# Voltage_converter_5V.net
KiCad netlist of a schematic drawn in EAGLE
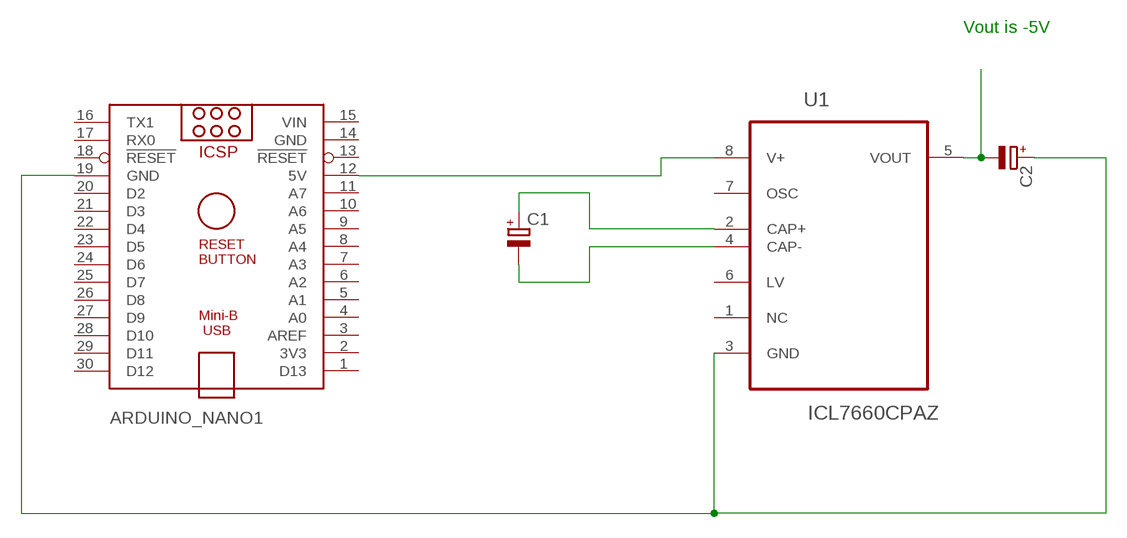
[diagram p0: schematic, sheet 1]

(export (version "E")
  (design (tool "Eeschema 10.0.6"))
  (components
    (comp (ref "ARDUINO_NANO1")
      (value "ARDUINO_NANO")
      (footprint "eagle-import:ARDUINO_NANO")
      (libsource (lib "eagle-import") (part "ARDUINO_NANO"))
    )
    (comp (ref "C1")
      (value "CPOL-EUE1.8-4")
      (footprint "eagle-import:E1,8-4")
      (libsource (lib "eagle-import") (part "CPOL-EUE1.8-4"))
    )
    (comp (ref "C2")
      (value "CPOL-EUE1.8-4")
      (footprint "eagle-import:E1,8-4")
      (libsource (lib "eagle-import") (part "CPOL-EUE1.8-4"))
    )
    (comp (ref "U1")
      (value "ICL7660CPAZ")
      (footprint "eagle-import:DIP254P762X533-8")
      (fields (field (name "MF") "Renesas Electronics"))
      (libsource (lib "eagle-import") (part "ICL7660CPAZ"))
    )
  )
  (nets
    (net (code "1") (name "/GND") (class "Default")
      (node (ref "ARDUINO_NANO1") (pin "14") (pinfunction "GND_14") (pintype "power_in"))
    )
    (net (code "2") (name "/VIN") (class "Default")
      (node (ref "ARDUINO_NANO1") (pin "15") (pinfunction "VIN_15") (pintype "power_in"))
    )
    (net (code "3") (name "Net-(ARDUINO_NANO1-5V)") (class "Default")
      (node (ref "ARDUINO_NANO1") (pin "12") (pinfunction "5V_12") (pintype "power_in"))
      (node (ref "U1") (pin "8") (pinfunction "V+_8") (pintype "power_in"))
    )
    (net (code "4") (name "Net-(U1-CAP+)") (class "Default")
      (node (ref "C1") (pin "+") (pinfunction "+_+") (pintype "passive"))
      (node (ref "U1") (pin "2") (pinfunction "CAP+_2") (pintype "input"))
    )
    (net (code "5") (name "Net-(U1-CAP-)") (class "Default")
      (node (ref "C1") (pin "-") (pinfunction "-_-") (pintype "passive"))
      (node (ref "U1") (pin "4") (pinfunction "CAP-_4") (pintype "input"))
    )
    (net (code "6") (name "Net-(U1-GND)") (class "Default")
      (node (ref "ARDUINO_NANO1") (pin "19") (pinfunction "GND_19") (pintype "power_in"))
      (node (ref "C2") (pin "+") (pinfunction "+_+") (pintype "passive"))
      (node (ref "U1") (pin "3") (pinfunction "GND_3") (pintype "passive"))
    )
    (net (code "7") (name "Net-(U1-VOUT)") (class "Default")
      (node (ref "C2") (pin "-") (pinfunction "-_-") (pintype "passive"))
      (node (ref "U1") (pin "5") (pinfunction "VOUT_5") (pintype "output"))
    )
    (net (code "8") (name "unconnected-(ARDUINO_NANO1-3V3-Pad2)") (class "Default")
      (node (ref "ARDUINO_NANO1") (pin "2") (pinfunction "3V3_2") (pintype "output"))
    )
    (net (code "9") (name "unconnected-(ARDUINO_NANO1-A0-Pad4)") (class "Default")
      (node (ref "ARDUINO_NANO1") (pin "4") (pinfunction "A0_4") (pintype "bidirectional"))
    )
    (net (code "10") (name "unconnected-(ARDUINO_NANO1-A1-Pad5)") (class "Default")
      (node (ref "ARDUINO_NANO1") (pin "5") (pinfunction "A1_5") (pintype "bidirectional"))
    )
    (net (code "11") (name "unconnected-(ARDUINO_NANO1-A2-Pad6)") (class "Default")
      (node (ref "ARDUINO_NANO1") (pin "6") (pinfunction "A2_6") (pintype "bidirectional"))
    )
    (net (code "12") (name "unconnected-(ARDUINO_NANO1-A3-Pad7)") (class "Default")
      (node (ref "ARDUINO_NANO1") (pin "7") (pinfunction "A3_7") (pintype "bidirectional"))
    )
    (net (code "13") (name "unconnected-(ARDUINO_NANO1-A4-Pad8)") (class "Default")
      (node (ref "ARDUINO_NANO1") (pin "8") (pinfunction "A4_8") (pintype "bidirectional"))
    )
    (net (code "14") (name "unconnected-(ARDUINO_NANO1-A5-Pad9)") (class "Default")
      (node (ref "ARDUINO_NANO1") (pin "9") (pinfunction "A5_9") (pintype "bidirectional"))
    )
    (net (code "15") (name "unconnected-(ARDUINO_NANO1-A6-Pad10)") (class "Default")
      (node (ref "ARDUINO_NANO1") (pin "10") (pinfunction "A6_10") (pintype "bidirectional"))
    )
    (net (code "16") (name "unconnected-(ARDUINO_NANO1-A7-Pad11)") (class "Default")
      (node (ref "ARDUINO_NANO1") (pin "11") (pinfunction "A7_11") (pintype "bidirectional"))
    )
    (net (code "17") (name "unconnected-(ARDUINO_NANO1-AREF-Pad3)") (class "Default")
      (node (ref "ARDUINO_NANO1") (pin "3") (pinfunction "AREF_3") (pintype "input"))
    )
    (net (code "18") (name "unconnected-(ARDUINO_NANO1-D2-Pad20)") (class "Default")
      (node (ref "ARDUINO_NANO1") (pin "20") (pinfunction "D2_20") (pintype "bidirectional"))
    )
    (net (code "19") (name "unconnected-(ARDUINO_NANO1-D3-Pad21)") (class "Default")
      (node (ref "ARDUINO_NANO1") (pin "21") (pinfunction "D3_21") (pintype "bidirectional"))
    )
    (net (code "20") (name "unconnected-(ARDUINO_NANO1-D4-Pad22)") (class "Default")
      (node (ref "ARDUINO_NANO1") (pin "22") (pinfunction "D4_22") (pintype "bidirectional"))
    )
    (net (code "21") (name "unconnected-(ARDUINO_NANO1-D5-Pad23)") (class "Default")
      (node (ref "ARDUINO_NANO1") (pin "23") (pinfunction "D5_23") (pintype "bidirectional"))
    )
    (net (code "22") (name "unconnected-(ARDUINO_NANO1-D6-Pad24)") (class "Default")
      (node (ref "ARDUINO_NANO1") (pin "24") (pinfunction "D6_24") (pintype "bidirectional"))
    )
    (net (code "23") (name "unconnected-(ARDUINO_NANO1-D7-Pad25)") (class "Default")
      (node (ref "ARDUINO_NANO1") (pin "25") (pinfunction "D7_25") (pintype "bidirectional"))
    )
    (net (code "24") (name "unconnected-(ARDUINO_NANO1-D8-Pad26)") (class "Default")
      (node (ref "ARDUINO_NANO1") (pin "26") (pinfunction "D8_26") (pintype "bidirectional"))
    )
    (net (code "25") (name "unconnected-(ARDUINO_NANO1-D9-Pad27)") (class "Default")
      (node (ref "ARDUINO_NANO1") (pin "27") (pinfunction "D9_27") (pintype "bidirectional"))
    )
    (net (code "26") (name "unconnected-(ARDUINO_NANO1-D10-Pad28)") (class "Default")
      (node (ref "ARDUINO_NANO1") (pin "28") (pinfunction "D10_28") (pintype "bidirectional"))
    )
    (net (code "27") (name "unconnected-(ARDUINO_NANO1-D11-Pad29)") (class "Default")
      (node (ref "ARDUINO_NANO1") (pin "29") (pinfunction "D11_29") (pintype "bidirectional"))
    )
    (net (code "28") (name "unconnected-(ARDUINO_NANO1-D12-Pad30)") (class "Default")
      (node (ref "ARDUINO_NANO1") (pin "30") (pinfunction "D12_30") (pintype "bidirectional"))
    )
    (net (code "29") (name "unconnected-(ARDUINO_NANO1-D13-Pad1)") (class "Default")
      (node (ref "ARDUINO_NANO1") (pin "1") (pinfunction "D13_1") (pintype "bidirectional"))
    )
    (net (code "30") (name "unconnected-(ARDUINO_NANO1-RX0-Pad17)") (class "Default")
      (node (ref "ARDUINO_NANO1") (pin "17") (pinfunction "RX0_17") (pintype "bidirectional"))
    )
    (net (code "31") (name "unconnected-(ARDUINO_NANO1-TX1-Pad16)") (class "Default")
      (node (ref "ARDUINO_NANO1") (pin "16") (pinfunction "TX1_16") (pintype "bidirectional"))
    )
    (net (code "32") (name "unconnected-(ARDUINO_NANO1-~{RESET}-Pad13)") (class "Default")
      (node (ref "ARDUINO_NANO1") (pin "13") (pinfunction "~{RESET}_13") (pintype "input"))
    )
    (net (code "33") (name "unconnected-(ARDUINO_NANO1-~{RESET}-Pad18)") (class "Default")
      (node (ref "ARDUINO_NANO1") (pin "18") (pinfunction "~{RESET}_18") (pintype "input"))
    )
    (net (code "34") (name "unconnected-(U1-LV-Pad6)") (class "Default")
      (node (ref "U1") (pin "6") (pinfunction "LV_6") (pintype "passive"))
    )
    (net (code "35") (name "unconnected-(U1-NC-Pad1)") (class "Default")
      (node (ref "U1") (pin "1") (pinfunction "NC_1") (pintype "no_connect"))
    )
    (net (code "36") (name "unconnected-(U1-OSC-Pad7)") (class "Default")
      (node (ref "U1") (pin "7") (pinfunction "OSC_7") (pintype "input"))
    )
  )
)
